# Power.net
KiCad netlist of a schematic drawn in Altium Designer
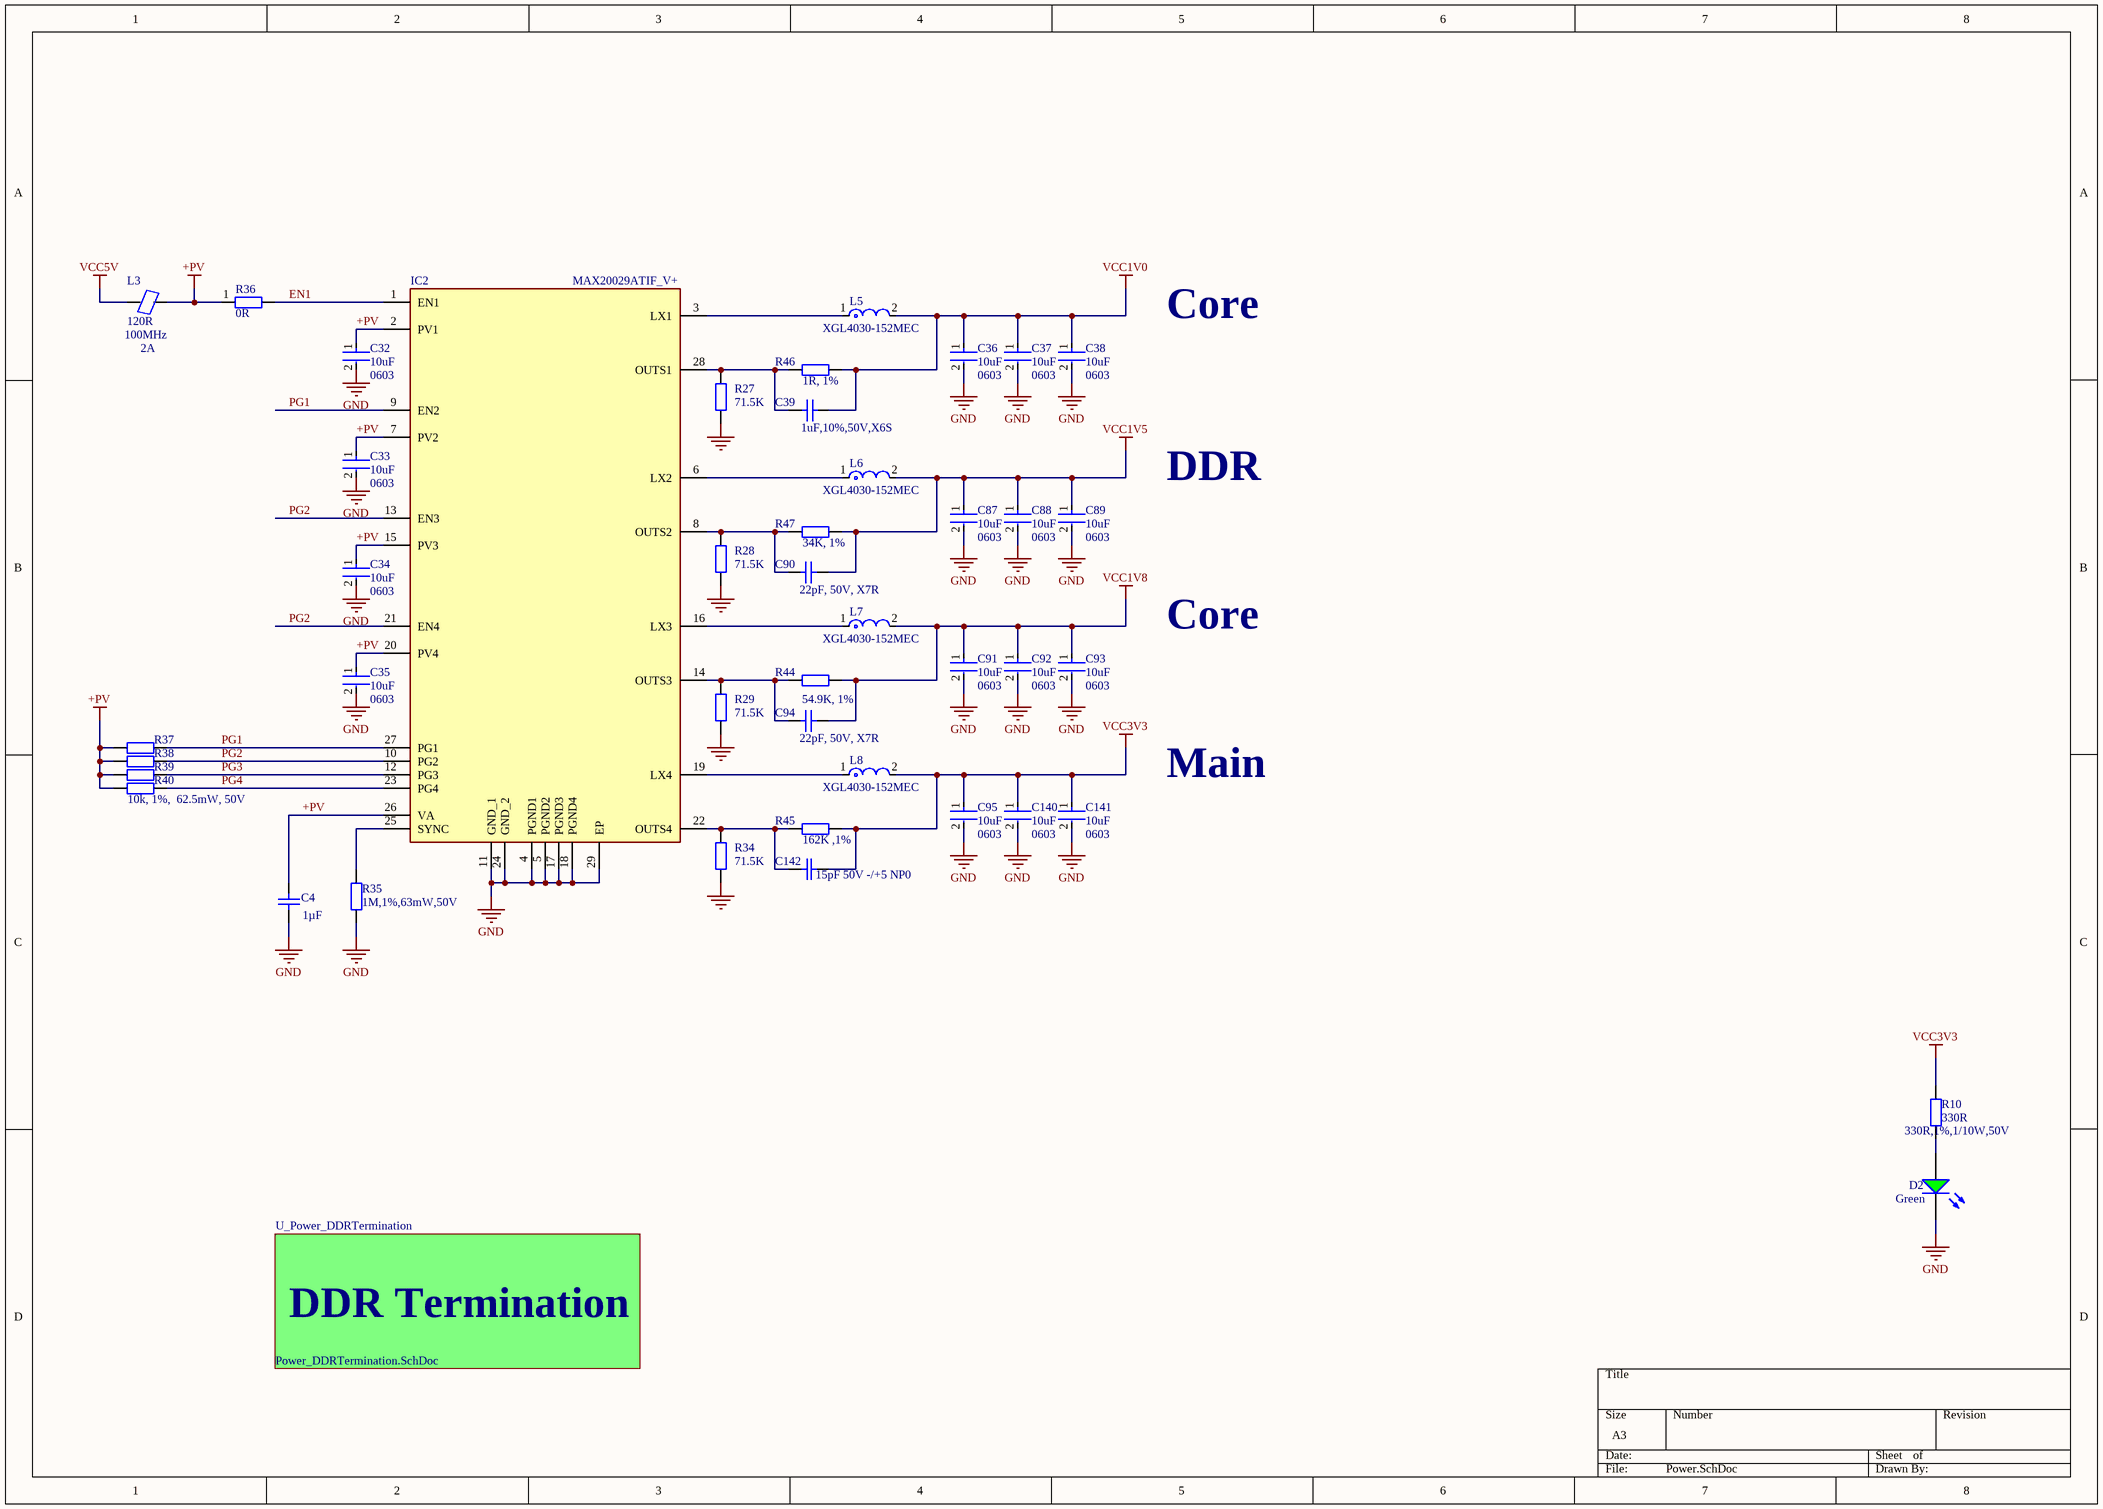
[diagram p0: Power.SchDoc]

(export (version "E")
  (design (tool "Eeschema 10.0.6"))
  (components
    (comp (ref "C4")
      (value "1µF")
      (footprint "CAP0402i")
      (description "0402, 1uF,  10%, 50V, X6S")
      (fields
        (field (name "PART NUMBER") "GRT155C81E105KE13D")
        (field (name "MANUFACTURER") "Murata")
        (field (name "CAPACITANCE") "1µF")
      )
      (libsource (lib "AmpherLib") (part "Cap_1uF_50V_X6S_0402"))
    )
    (comp (ref "C32")
      (value "GRM188R60J106ME47D")
      (footprint "FP-GRM188-0_1-e0_2_0_55-IPC_A")
      (description "Chip Multilayer Ceramic Capacitors for General Purpose, 0603, 10uF, X5R, 15%, 20%, 6.3V")
      (fields
        (field (name "CAPACITANCE") "10uF")
        (field (name "CASE/PACKAGE") "0603")
        (field (name "VOLTAGE") "6.3V")
        (field (name "TOLERANCE") "20%")
      )
      (libsource (lib "Altium Content Vault") (part "02cd4be3c70576c341d710602a673aa"))
    )
    (comp (ref "C33")
      (value "GRM188R60J106ME47D")
      (footprint "FP-GRM188-0_1-e0_2_0_55-IPC_A")
      (description "Chip Multilayer Ceramic Capacitors for General Purpose, 0603, 10uF, X5R, 15%, 20%, 6.3V")
      (fields
        (field (name "CAPACITANCE") "10uF")
        (field (name "CASE/PACKAGE") "0603")
        (field (name "VOLTAGE") "6.3V")
        (field (name "TOLERANCE") "20%")
      )
      (libsource (lib "Altium Content Vault") (part "02cd4be3c70576c341d710602a673aa"))
    )
    (comp (ref "C34")
      (value "GRM188R60J106ME47D")
      (footprint "FP-GRM188-0_1-e0_2_0_55-IPC_A")
      (description "Chip Multilayer Ceramic Capacitors for General Purpose, 0603, 10uF, X5R, 15%, 20%, 6.3V")
      (fields
        (field (name "CAPACITANCE") "10uF")
        (field (name "CASE/PACKAGE") "0603")
        (field (name "VOLTAGE") "6.3V")
        (field (name "TOLERANCE") "20%")
      )
      (libsource (lib "Altium Content Vault") (part "02cd4be3c70576c341d710602a673aa"))
    )
    (comp (ref "C35")
      (value "GRM188R60J106ME47D")
      (footprint "FP-GRM188-0_1-e0_2_0_55-IPC_A")
      (description "Chip Multilayer Ceramic Capacitors for General Purpose, 0603, 10uF, X5R, 15%, 20%, 6.3V")
      (fields
        (field (name "CAPACITANCE") "10uF")
        (field (name "CASE/PACKAGE") "0603")
        (field (name "VOLTAGE") "6.3V")
        (field (name "TOLERANCE") "20%")
      )
      (libsource (lib "Altium Content Vault") (part "02cd4be3c70576c341d710602a673aa"))
    )
    (comp (ref "C36")
      (value "GRM188R60J106ME47D")
      (footprint "FP-GRM188-0_1-e0_2_0_55-IPC_A")
      (description "Chip Multilayer Ceramic Capacitors for General Purpose, 0603, 10uF, X5R, 15%, 20%, 6.3V")
      (fields
        (field (name "CAPACITANCE") "10uF")
        (field (name "CASE/PACKAGE") "0603")
        (field (name "VOLTAGE") "6.3V")
        (field (name "TOLERANCE") "20%")
      )
      (libsource (lib "Altium Content Vault") (part "02cd4be3c70576c341d710602a673aa"))
    )
    (comp (ref "C37")
      (value "GRM188R60J106ME47D")
      (footprint "FP-GRM188-0_1-e0_2_0_55-IPC_A")
      (description "Chip Multilayer Ceramic Capacitors for General Purpose, 0603, 10uF, X5R, 15%, 20%, 6.3V")
      (fields
        (field (name "CAPACITANCE") "10uF")
        (field (name "CASE/PACKAGE") "0603")
        (field (name "VOLTAGE") "6.3V")
        (field (name "TOLERANCE") "20%")
      )
      (libsource (lib "Altium Content Vault") (part "02cd4be3c70576c341d710602a673aa"))
    )
    (comp (ref "C38")
      (value "GRM188R60J106ME47D")
      (footprint "FP-GRM188-0_1-e0_2_0_55-IPC_A")
      (description "Chip Multilayer Ceramic Capacitors for General Purpose, 0603, 10uF, X5R, 15%, 20%, 6.3V")
      (fields
        (field (name "CAPACITANCE") "10uF")
        (field (name "CASE/PACKAGE") "0603")
        (field (name "VOLTAGE") "6.3V")
        (field (name "TOLERANCE") "20%")
      )
      (libsource (lib "Altium Content Vault") (part "02cd4be3c70576c341d710602a673aa"))
    )
    (comp (ref "C39")
      (value "1uF,10%,50V,X6S")
      (footprint "CAP0402i")
      (description "0402, 1uF,  10%, 50V, X6S")
      (fields (field (name "PART NUMBER") "GRT155C81E105KE13D") (field (name "MANUFACTURER") "Murata"))
      (libsource (lib "AmpherLib") (part "Cap_1uF_50V_X6S_0402"))
    )
    (comp (ref "C87")
      (value "GRM188R60J106ME47D")
      (footprint "FP-GRM188-0_1-e0_2_0_55-IPC_A")
      (description "Chip Multilayer Ceramic Capacitors for General Purpose, 0603, 10uF, X5R, 15%, 20%, 6.3V")
      (fields
        (field (name "CAPACITANCE") "10uF")
        (field (name "CASE/PACKAGE") "0603")
        (field (name "VOLTAGE") "6.3V")
        (field (name "TOLERANCE") "20%")
      )
      (libsource (lib "Altium Content Vault") (part "02cd4be3c70576c341d710602a673aa"))
    )
    (comp (ref "C88")
      (value "GRM188R60J106ME47D")
      (footprint "FP-GRM188-0_1-e0_2_0_55-IPC_A")
      (description "Chip Multilayer Ceramic Capacitors for General Purpose, 0603, 10uF, X5R, 15%, 20%, 6.3V")
      (fields
        (field (name "CAPACITANCE") "10uF")
        (field (name "CASE/PACKAGE") "0603")
        (field (name "VOLTAGE") "6.3V")
        (field (name "TOLERANCE") "20%")
      )
      (libsource (lib "Altium Content Vault") (part "02cd4be3c70576c341d710602a673aa"))
    )
    (comp (ref "C89")
      (value "GRM188R60J106ME47D")
      (footprint "FP-GRM188-0_1-e0_2_0_55-IPC_A")
      (description "Chip Multilayer Ceramic Capacitors for General Purpose, 0603, 10uF, X5R, 15%, 20%, 6.3V")
      (fields
        (field (name "CAPACITANCE") "10uF")
        (field (name "CASE/PACKAGE") "0603")
        (field (name "VOLTAGE") "6.3V")
        (field (name "TOLERANCE") "20%")
      )
      (libsource (lib "Altium Content Vault") (part "02cd4be3c70576c341d710602a673aa"))
    )
    (comp (ref "C90")
      (value "22pF, 50V, X7R")
      (footprint "cap0402i")
      (description "Multilayer Ceramic Capacitor, AEC-Q200 CGA Series, 22 pF, - 5%, C0G / NP0, 50 V")
      (fields (field (name "TOLERANCE") "5%") (field (name "PART NUMBER") "CGA2B2C0G1H220J050BA"))
      (libsource (lib "AmpherLib") (part "CAP_22pF_50V_X7R_0402"))
    )
    (comp (ref "C91")
      (value "GRM188R60J106ME47D")
      (footprint "FP-GRM188-0_1-e0_2_0_55-IPC_A")
      (description "Chip Multilayer Ceramic Capacitors for General Purpose, 0603, 10uF, X5R, 15%, 20%, 6.3V")
      (fields
        (field (name "CAPACITANCE") "10uF")
        (field (name "CASE/PACKAGE") "0603")
        (field (name "VOLTAGE") "6.3V")
        (field (name "TOLERANCE") "20%")
      )
      (libsource (lib "Altium Content Vault") (part "02cd4be3c70576c341d710602a673aa"))
    )
    (comp (ref "C92")
      (value "GRM188R60J106ME47D")
      (footprint "FP-GRM188-0_1-e0_2_0_55-IPC_A")
      (description "Chip Multilayer Ceramic Capacitors for General Purpose, 0603, 10uF, X5R, 15%, 20%, 6.3V")
      (fields
        (field (name "CAPACITANCE") "10uF")
        (field (name "CASE/PACKAGE") "0603")
        (field (name "VOLTAGE") "6.3V")
        (field (name "TOLERANCE") "20%")
      )
      (libsource (lib "Altium Content Vault") (part "02cd4be3c70576c341d710602a673aa"))
    )
    (comp (ref "C93")
      (value "GRM188R60J106ME47D")
      (footprint "FP-GRM188-0_1-e0_2_0_55-IPC_A")
      (description "Chip Multilayer Ceramic Capacitors for General Purpose, 0603, 10uF, X5R, 15%, 20%, 6.3V")
      (fields
        (field (name "CAPACITANCE") "10uF")
        (field (name "CASE/PACKAGE") "0603")
        (field (name "VOLTAGE") "6.3V")
        (field (name "TOLERANCE") "20%")
      )
      (libsource (lib "Altium Content Vault") (part "02cd4be3c70576c341d710602a673aa"))
    )
    (comp (ref "C94")
      (value "22pF, 50V, X7R")
      (footprint "cap0402i")
      (description "Multilayer Ceramic Capacitor, AEC-Q200 CGA Series, 22 pF, - 5%, C0G / NP0, 50 V")
      (fields (field (name "TOLERANCE") "5%") (field (name "PART NUMBER") "CGA2B2C0G1H220J050BA"))
      (libsource (lib "AmpherLib") (part "CAP_22pF_50V_X7R_0402"))
    )
    (comp (ref "C95")
      (value "GRM188R60J106ME47D")
      (footprint "FP-GRM188-0_1-e0_2_0_55-IPC_A")
      (description "Chip Multilayer Ceramic Capacitors for General Purpose, 0603, 10uF, X5R, 15%, 20%, 6.3V")
      (fields
        (field (name "CAPACITANCE") "10uF")
        (field (name "CASE/PACKAGE") "0603")
        (field (name "VOLTAGE") "6.3V")
        (field (name "TOLERANCE") "20%")
      )
      (libsource (lib "Altium Content Vault") (part "02cd4be3c70576c341d710602a673aa"))
    )
    (comp (ref "C140")
      (value "GRM188R60J106ME47D")
      (footprint "FP-GRM188-0_1-e0_2_0_55-IPC_A")
      (description "Chip Multilayer Ceramic Capacitors for General Purpose, 0603, 10uF, X5R, 15%, 20%, 6.3V")
      (fields
        (field (name "CAPACITANCE") "10uF")
        (field (name "CASE/PACKAGE") "0603")
        (field (name "VOLTAGE") "6.3V")
        (field (name "TOLERANCE") "20%")
      )
      (libsource (lib "Altium Content Vault") (part "02cd4be3c70576c341d710602a673aa"))
    )
    (comp (ref "C141")
      (value "GRM188R60J106ME47D")
      (footprint "FP-GRM188-0_1-e0_2_0_55-IPC_A")
      (description "Chip Multilayer Ceramic Capacitors for General Purpose, 0603, 10uF, X5R, 15%, 20%, 6.3V")
      (fields
        (field (name "CAPACITANCE") "10uF")
        (field (name "CASE/PACKAGE") "0603")
        (field (name "VOLTAGE") "6.3V")
        (field (name "TOLERANCE") "20%")
      )
      (libsource (lib "Altium Content Vault") (part "02cd4be3c70576c341d710602a673aa"))
    )
    (comp (ref "C142")
      (value "15pF 50V -/+5 NP0")
      (footprint "CAP0402i")
      (description "0402 15 pF 50 V ±5 % Tolerance NP0 SMT Multilayer Ceramic Capacitor")
      (fields (field (name "VOLTAGE") "50V") (field (name "TOLERANCE") "5%"))
      (libsource (lib "AmpherLib") (part "Cap_15pF_50V_0402"))
    )
    (comp (ref "D2")
      (value "Green")
      (footprint "0805_LED_S1")
      (description "发光二极管")
      (libsource (lib "LED") (part "0805 翠绿"))
    )
    (comp (ref "IC2")
      (value "MAX20029ATIF_V+")
      (footprint "PCB1:QFN50P500X500X80-29N")
      (description "DC to DC Converter Quad Step-Down 3V to 5.5V Automotive 28-Pin TQFN Tube")
      (fields
        (field (name "MANUFACTURER_PART_NUMBER") "MAX20029ATIF/V+")
        (field (name "MOUSER PART NUMBER") "700-MAX20029ATIF/V+")
      )
      (libsource (lib "SamacSys") (part "MAX20029ATIF_V+"))
    )
    (comp (ref "L3")
      (value "FB_120@100MHz")
      (footprint "CAP0402i")
      (description "Ferrite Beads Multi-Layer 120Ohm 25% 100MHz 2A 0.055Ohm DCR 0402 T/R")
      (fields
        (field (name "TOLERANCE") "25%")
        (field (name "IMPEDANCE") "120R")
        (field (name "MAX DC CURRENT") "2A")
        (field (name "TEST FREQUENCY") "100MHz")
        (field (name "PART NUMBER") "BLM15PX121SN1D")
      )
      (libsource (lib "AmpherLib") (part "Ferrite Bead_ 0402_120R_100MHz_2A"))
    )
    (comp (ref "L5")
      (value "XGL4030-152MEC")
      (footprint "FP-XGL4030-MFG")
      (description "SHIELDED POWER INDUCTORS, 1.5UH")
      (libsource (lib "Altium Content Vault") (part "4cc4b267dca4c8e51f7102f422741d8"))
    )
    (comp (ref "L6")
      (value "XGL4030-152MEC")
      (footprint "FP-XGL4030-MFG")
      (description "SHIELDED POWER INDUCTORS, 1.5UH")
      (libsource (lib "Altium Content Vault") (part "4cc4b267dca4c8e51f7102f422741d8"))
    )
    (comp (ref "L7")
      (value "XGL4030-152MEC")
      (footprint "FP-XGL4030-MFG")
      (description "SHIELDED POWER INDUCTORS, 1.5UH")
      (libsource (lib "Altium Content Vault") (part "4cc4b267dca4c8e51f7102f422741d8"))
    )
    (comp (ref "L8")
      (value "XGL4030-152MEC")
      (footprint "FP-XGL4030-MFG")
      (description "SHIELDED POWER INDUCTORS, 1.5UH")
      (libsource (lib "Altium Content Vault") (part "4cc4b267dca4c8e51f7102f422741d8"))
    )
    (comp (ref "R10")
      (value "330R")
      (footprint "RES0402i")
      (description "Res Thick Film 0402 330 Ohm 1% 1/16W ±100ppm/°C Molded SMD Paper T/R")
      (fields
        (field (name "PART NUMBER") "CRCW0402330RFKED")
        (field (name "VOLTAGE") "50")
        (field (name "ALTIUM_VALUE") "330R,1%,1/10W,50V")
      )
      (libsource (lib "AmpherLib") (part "Res_330R_1%_50V_0402"))
    )
    (comp (ref "R27")
      (value "71.5K")
      (footprint "RES0402i")
      (description "Res Thick Film 0402 71.5K Ohm 1% 1/10W ±100ppm/°C Molded SMD Punched Carrier T/R")
      (fields
        (field (name "PART NUMBER") "ERJ-2RKF7152X")
        (field (name "TOLERANCE") "±1%")
        (field (name "RESISTANCE") "71.5K")
      )
      (libsource (lib "AmpherLib") (part "Res_71.5K_1%_1/10W_0402"))
    )
    (comp (ref "R28")
      (value "71.5K")
      (footprint "RES0402i")
      (description "Res Thick Film 0402 71.5K Ohm 1% 1/10W ±100ppm/°C Molded SMD Punched Carrier T/R")
      (fields
        (field (name "PART NUMBER") "ERJ-2RKF7152X")
        (field (name "TOLERANCE") "±1%")
        (field (name "RESISTANCE") "71.5K")
      )
      (libsource (lib "AmpherLib") (part "Res_71.5K_1%_1/10W_0402"))
    )
    (comp (ref "R29")
      (value "71.5K")
      (footprint "RES0402i")
      (description "Res Thick Film 0402 71.5K Ohm 1% 1/10W ±100ppm/°C Molded SMD Punched Carrier T/R")
      (fields
        (field (name "PART NUMBER") "ERJ-2RKF7152X")
        (field (name "TOLERANCE") "±1%")
        (field (name "RESISTANCE") "71.5K")
      )
      (libsource (lib "AmpherLib") (part "Res_71.5K_1%_1/10W_0402"))
    )
    (comp (ref "R34")
      (value "71.5K")
      (footprint "RES0402i")
      (description "Res Thick Film 0402 71.5K Ohm 1% 1/10W ±100ppm/°C Molded SMD Punched Carrier T/R")
      (fields
        (field (name "PART NUMBER") "ERJ-2RKF7152X")
        (field (name "TOLERANCE") "±1%")
        (field (name "RESISTANCE") "71.5K")
      )
      (libsource (lib "AmpherLib") (part "Res_71.5K_1%_1/10W_0402"))
    )
    (comp (ref "R35")
      (value "1M,1%,63mW,50V")
      (footprint "RES0402i")
      (description "0402,1M,1%,63mW,50V")
      (fields (field (name "PART NUMBER") "ERJ-2RKF1004X") (field (name "VOLTAGE") "50V"))
      (libsource (lib "AmpherLib") (part "Res_1M_1%_0402"))
    )
    (comp (ref "R36")
      (value "0R")
      (footprint "RES0402i")
      (description "0402, 0R")
      (fields (field (name "PART NUMBER") "CRCW04020000Z0EDC") (field (name "VOLTAGE") "50V"))
      (libsource (lib "AmpherLib") (part "Res_0R_0402"))
    )
    (comp (ref "R37")
      (value "10 kOhms")
      (footprint "RES0402i")
      (description "0402, 10K 1%,  62.5mW, 50V")
      (fields (field (name "PART NUMBER") "CR0402-FX-1002GLF") (field (name "VOLTAGE") "50V"))
      (libsource (lib "AmpherLib") (part "Res_10k_1%_0402"))
    )
    (comp (ref "R38")
      (value "10 kOhms")
      (footprint "RES0402i")
      (description "0402, 10K 1%,  62.5mW, 50V")
      (fields (field (name "PART NUMBER") "CR0402-FX-1002GLF") (field (name "VOLTAGE") "50V"))
      (libsource (lib "AmpherLib") (part "Res_10k_1%_0402"))
    )
    (comp (ref "R39")
      (value "10 kOhms")
      (footprint "RES0402i")
      (description "0402, 10K 1%,  62.5mW, 50V")
      (fields (field (name "PART NUMBER") "CR0402-FX-1002GLF") (field (name "VOLTAGE") "50V"))
      (libsource (lib "AmpherLib") (part "Res_10k_1%_0402"))
    )
    (comp (ref "R40")
      (value "10k, 1%,  62.5mW, 50V")
      (footprint "RES0402i")
      (description "0402, 10K 1%,  62.5mW, 50V")
      (fields (field (name "PART NUMBER") "CR0402-FX-1002GLF") (field (name "VOLTAGE") "50V"))
      (libsource (lib "AmpherLib") (part "Res_10k_1%_0402"))
    )
    (comp (ref "R44")
      (value "54.9K, 1%")
      (footprint "RES0402i")
      (description "SMD Chip Resistor, 54.9 kOhm, ± 1%, 100 mW, 0402 [1005 Metric], Thick Film, Precision")
      (fields (field (name "TOLERANCE") "±1%") (field (name "MANUFACTURER") "Panasonic"))
      (libsource (lib "AmpherLib") (part "Res_A_0402__________________________Template_1_1_1_1_1"))
    )
    (comp (ref "R45")
      (value "162K ,1%")
      (footprint "RES0402i")
      (description "Res Thick Film 0402 162K Ohm 1% 0.1W ±100ppm/°C Molded SMD Punched Carrier T/R")
      (fields (field (name "TOLERANCE") "±1%") (field (name "MANUFACTURER") "Panasonic"))
      (libsource (lib "AmpherLib") (part "Res_A_0402__________________________Template_1_1_1_1_1"))
    )
    (comp (ref "R46")
      (value "1R, 1%")
      (footprint "RES0402i")
      (description "SMD Chip Resistor, 1 Ohm, ± 5%, 63 mW, 0402 [1005 Metric], Thick Film, General Purpose")
      (fields (field (name "TOLERANCE") "±1%") (field (name "MANUFACTURER") "Vishay Dale"))
      (libsource (lib "AmpherLib") (part "Res_A_0402__________________________Template_1_1_1_1_1"))
    )
    (comp (ref "R47")
      (value "34K, 1%")
      (footprint "RES0402i")
      (description "SMD Chip Resistor, 34 kOhm, ± 1%, 63 mW, 0402 [1005 Metric], Thick Film, General Purpose")
      (fields (field (name "TOLERANCE") "±1%") (field (name "MANUFACTURER") "Vishay"))
      (libsource (lib "AmpherLib") (part "Res_A_0402__________________________Template_1_1_1_1_1"))
    )
  )
  (nets
    (net (code "1") (name "+PV") (class "Default")
      (node (ref "C32") (pin "1") (pinfunction "1_1") (pintype "passive"))
      (node (ref "C33") (pin "1") (pinfunction "1_1") (pintype "passive"))
      (node (ref "C34") (pin "1") (pinfunction "1_1") (pintype "passive"))
      (node (ref "C35") (pin "1") (pinfunction "1_1") (pintype "passive"))
      (node (ref "C4") (pin "2") (pinfunction "2_2") (pintype "passive"))
      (node (ref "IC2") (pin "15") (pinfunction "PV3_15") (pintype "passive"))
      (node (ref "IC2") (pin "2") (pinfunction "PV1_2") (pintype "passive"))
      (node (ref "IC2") (pin "20") (pinfunction "PV4_20") (pintype "passive"))
      (node (ref "IC2") (pin "26") (pinfunction "VA_26") (pintype "passive"))
      (node (ref "IC2") (pin "7") (pinfunction "PV2_7") (pintype "passive"))
      (node (ref "L3") (pin "2") (pinfunction "2_2") (pintype "passive"))
      (node (ref "R36") (pin "1") (pinfunction "1_1") (pintype "passive"))
      (node (ref "R37") (pin "1") (pinfunction "1_1") (pintype "passive"))
      (node (ref "R38") (pin "1") (pinfunction "1_1") (pintype "passive"))
      (node (ref "R39") (pin "1") (pinfunction "1_1") (pintype "passive"))
      (node (ref "R40") (pin "1") (pinfunction "1_1") (pintype "passive"))
    )
    (net (code "2") (name "/EN1") (class "Default")
      (node (ref "IC2") (pin "1") (pinfunction "EN1_1") (pintype "passive"))
      (node (ref "R36") (pin "2") (pinfunction "2_2") (pintype "passive"))
    )
    (net (code "3") (name "/PG1") (class "Default")
      (node (ref "IC2") (pin "27") (pinfunction "PG1_27") (pintype "passive"))
      (node (ref "IC2") (pin "9") (pinfunction "EN2_9") (pintype "passive"))
      (node (ref "R37") (pin "2") (pinfunction "2_2") (pintype "passive"))
    )
    (net (code "4") (name "/PG2") (class "Default")
      (node (ref "IC2") (pin "10") (pinfunction "PG2_10") (pintype "passive"))
      (node (ref "IC2") (pin "13") (pinfunction "EN3_13") (pintype "passive"))
      (node (ref "IC2") (pin "21") (pinfunction "EN4_21") (pintype "passive"))
      (node (ref "R38") (pin "2") (pinfunction "2_2") (pintype "passive"))
    )
    (net (code "5") (name "/PG3") (class "Default")
      (node (ref "IC2") (pin "12") (pinfunction "PG3_12") (pintype "passive"))
      (node (ref "R39") (pin "2") (pinfunction "2_2") (pintype "passive"))
    )
    (net (code "6") (name "/PG4") (class "Default")
      (node (ref "IC2") (pin "23") (pinfunction "PG4_23") (pintype "passive"))
      (node (ref "R40") (pin "2") (pinfunction "2_2") (pintype "passive"))
    )
    (net (code "7") (name "GND") (class "Default")
      (node (ref "C140") (pin "2") (pinfunction "2_2") (pintype "passive"))
      (node (ref "C141") (pin "2") (pinfunction "2_2") (pintype "passive"))
      (node (ref "C32") (pin "2") (pinfunction "2_2") (pintype "passive"))
      (node (ref "C33") (pin "2") (pinfunction "2_2") (pintype "passive"))
      (node (ref "C34") (pin "2") (pinfunction "2_2") (pintype "passive"))
      (node (ref "C35") (pin "2") (pinfunction "2_2") (pintype "passive"))
      (node (ref "C36") (pin "2") (pinfunction "2_2") (pintype "passive"))
      (node (ref "C37") (pin "2") (pinfunction "2_2") (pintype "passive"))
      (node (ref "C38") (pin "2") (pinfunction "2_2") (pintype "passive"))
      (node (ref "C4") (pin "1") (pinfunction "1_1") (pintype "passive"))
      (node (ref "C87") (pin "2") (pinfunction "2_2") (pintype "passive"))
      (node (ref "C88") (pin "2") (pinfunction "2_2") (pintype "passive"))
      (node (ref "C89") (pin "2") (pinfunction "2_2") (pintype "passive"))
      (node (ref "C91") (pin "2") (pinfunction "2_2") (pintype "passive"))
      (node (ref "C92") (pin "2") (pinfunction "2_2") (pintype "passive"))
      (node (ref "C93") (pin "2") (pinfunction "2_2") (pintype "passive"))
      (node (ref "C95") (pin "2") (pinfunction "2_2") (pintype "passive"))
      (node (ref "D2") (pin "K") (pinfunction "K_K") (pintype "passive"))
      (node (ref "IC2") (pin "11") (pinfunction "GND_1_11") (pintype "passive"))
      (node (ref "IC2") (pin "17") (pinfunction "PGND3_17") (pintype "passive"))
      (node (ref "IC2") (pin "18") (pinfunction "PGND4_18") (pintype "passive"))
      (node (ref "IC2") (pin "24") (pinfunction "GND_2_24") (pintype "passive"))
      (node (ref "IC2") (pin "29") (pinfunction "EP_29") (pintype "passive"))
      (node (ref "IC2") (pin "4") (pinfunction "PGND1_4") (pintype "passive"))
      (node (ref "IC2") (pin "5") (pinfunction "PGND2_5") (pintype "passive"))
      (node (ref "R27") (pin "1") (pinfunction "1_1") (pintype "passive"))
      (node (ref "R28") (pin "1") (pinfunction "1_1") (pintype "passive"))
      (node (ref "R29") (pin "1") (pinfunction "1_1") (pintype "passive"))
      (node (ref "R34") (pin "1") (pinfunction "1_1") (pintype "passive"))
      (node (ref "R35") (pin "1") (pinfunction "1_1") (pintype "passive"))
    )
    (net (code "8") (name "Net-(D2-PadA)") (class "Default")
      (node (ref "D2") (pin "A") (pinfunction "A_A") (pintype "passive"))
      (node (ref "R10") (pin "1") (pinfunction "1_1") (pintype "passive"))
    )
    (net (code "9") (name "Net-(IC2-LX1)") (class "Default")
      (node (ref "IC2") (pin "3") (pinfunction "LX1_3") (pintype "passive"))
      (node (ref "L5") (pin "1") (pinfunction "1_1") (pintype "passive"))
    )
    (net (code "10") (name "Net-(IC2-LX2)") (class "Default")
      (node (ref "IC2") (pin "6") (pinfunction "LX2_6") (pintype "passive"))
      (node (ref "L6") (pin "1") (pinfunction "1_1") (pintype "passive"))
    )
    (net (code "11") (name "Net-(IC2-LX3)") (class "Default")
      (node (ref "IC2") (pin "16") (pinfunction "LX3_16") (pintype "passive"))
      (node (ref "L7") (pin "1") (pinfunction "1_1") (pintype "passive"))
    )
    (net (code "12") (name "Net-(IC2-LX4)") (class "Default")
      (node (ref "IC2") (pin "19") (pinfunction "LX4_19") (pintype "passive"))
      (node (ref "L8") (pin "1") (pinfunction "1_1") (pintype "passive"))
    )
    (net (code "13") (name "Net-(IC2-OUTS1)") (class "Default")
      (node (ref "C39") (pin "1") (pinfunction "1_1") (pintype "passive"))
      (node (ref "IC2") (pin "28") (pinfunction "OUTS1_28") (pintype "passive"))
      (node (ref "R27") (pin "2") (pinfunction "2_2") (pintype "passive"))
      (node (ref "R46") (pin "1") (pinfunction "1_1") (pintype "passive"))
    )
    (net (code "14") (name "Net-(IC2-OUTS2)") (class "Default")
      (node (ref "C90") (pin "1") (pinfunction "1_1") (pintype "passive"))
      (node (ref "IC2") (pin "8") (pinfunction "OUTS2_8") (pintype "passive"))
      (node (ref "R28") (pin "2") (pinfunction "2_2") (pintype "passive"))
      (node (ref "R47") (pin "1") (pinfunction "1_1") (pintype "passive"))
    )
    (net (code "15") (name "Net-(IC2-OUTS3)") (class "Default")
      (node (ref "C94") (pin "1") (pinfunction "1_1") (pintype "passive"))
      (node (ref "IC2") (pin "14") (pinfunction "OUTS3_14") (pintype "passive"))
      (node (ref "R29") (pin "2") (pinfunction "2_2") (pintype "passive"))
      (node (ref "R44") (pin "1") (pinfunction "1_1") (pintype "passive"))
    )
    (net (code "16") (name "Net-(IC2-OUTS4)") (class "Default")
      (node (ref "C142") (pin "2") (pinfunction "2_2") (pintype "passive"))
      (node (ref "IC2") (pin "22") (pinfunction "OUTS4_22") (pintype "passive"))
      (node (ref "R34") (pin "2") (pinfunction "2_2") (pintype "passive"))
      (node (ref "R45") (pin "1") (pinfunction "1_1") (pintype "passive"))
    )
    (net (code "17") (name "Net-(IC2-SYNC)") (class "Default")
      (node (ref "IC2") (pin "25") (pinfunction "SYNC_25") (pintype "passive"))
      (node (ref "R35") (pin "2") (pinfunction "2_2") (pintype "passive"))
    )
    (net (code "18") (name "VCC1V0") (class "Default")
      (node (ref "C36") (pin "1") (pinfunction "1_1") (pintype "passive"))
      (node (ref "C37") (pin "1") (pinfunction "1_1") (pintype "passive"))
      (node (ref "C38") (pin "1") (pinfunction "1_1") (pintype "passive"))
      (node (ref "C39") (pin "2") (pinfunction "2_2") (pintype "passive"))
      (node (ref "L5") (pin "2") (pinfunction "2_2") (pintype "passive"))
      (node (ref "R46") (pin "2") (pinfunction "2_2") (pintype "passive"))
    )
    (net (code "19") (name "VCC1V5") (class "Default")
      (node (ref "C87") (pin "1") (pinfunction "1_1") (pintype "passive"))
      (node (ref "C88") (pin "1") (pinfunction "1_1") (pintype "passive"))
      (node (ref "C89") (pin "1") (pinfunction "1_1") (pintype "passive"))
      (node (ref "C90") (pin "2") (pinfunction "2_2") (pintype "passive"))
      (node (ref "L6") (pin "2") (pinfunction "2_2") (pintype "passive"))
      (node (ref "R47") (pin "2") (pinfunction "2_2") (pintype "passive"))
    )
    (net (code "20") (name "VCC1V8") (class "Default")
      (node (ref "C91") (pin "1") (pinfunction "1_1") (pintype "passive"))
      (node (ref "C92") (pin "1") (pinfunction "1_1") (pintype "passive"))
      (node (ref "C93") (pin "1") (pinfunction "1_1") (pintype "passive"))
      (node (ref "C94") (pin "2") (pinfunction "2_2") (pintype "passive"))
      (node (ref "L7") (pin "2") (pinfunction "2_2") (pintype "passive"))
      (node (ref "R44") (pin "2") (pinfunction "2_2") (pintype "passive"))
    )
    (net (code "21") (name "VCC3V3") (class "Default")
      (node (ref "C140") (pin "1") (pinfunction "1_1") (pintype "passive"))
      (node (ref "C141") (pin "1") (pinfunction "1_1") (pintype "passive"))
      (node (ref "C142") (pin "1") (pinfunction "1_1") (pintype "passive"))
      (node (ref "C95") (pin "1") (pinfunction "1_1") (pintype "passive"))
      (node (ref "L8") (pin "2") (pinfunction "2_2") (pintype "passive"))
      (node (ref "R10") (pin "2") (pinfunction "2_2") (pintype "passive"))
      (node (ref "R45") (pin "2") (pinfunction "2_2") (pintype "passive"))
    )
    (net (code "22") (name "VCC5V") (class "Default")
      (node (ref "L3") (pin "1") (pinfunction "1_1") (pintype "passive"))
    )
  )
)
